# FPGA_POWER_AND_CONFIGURATION.net
KiCad netlist of a schematic drawn in Altium Designer
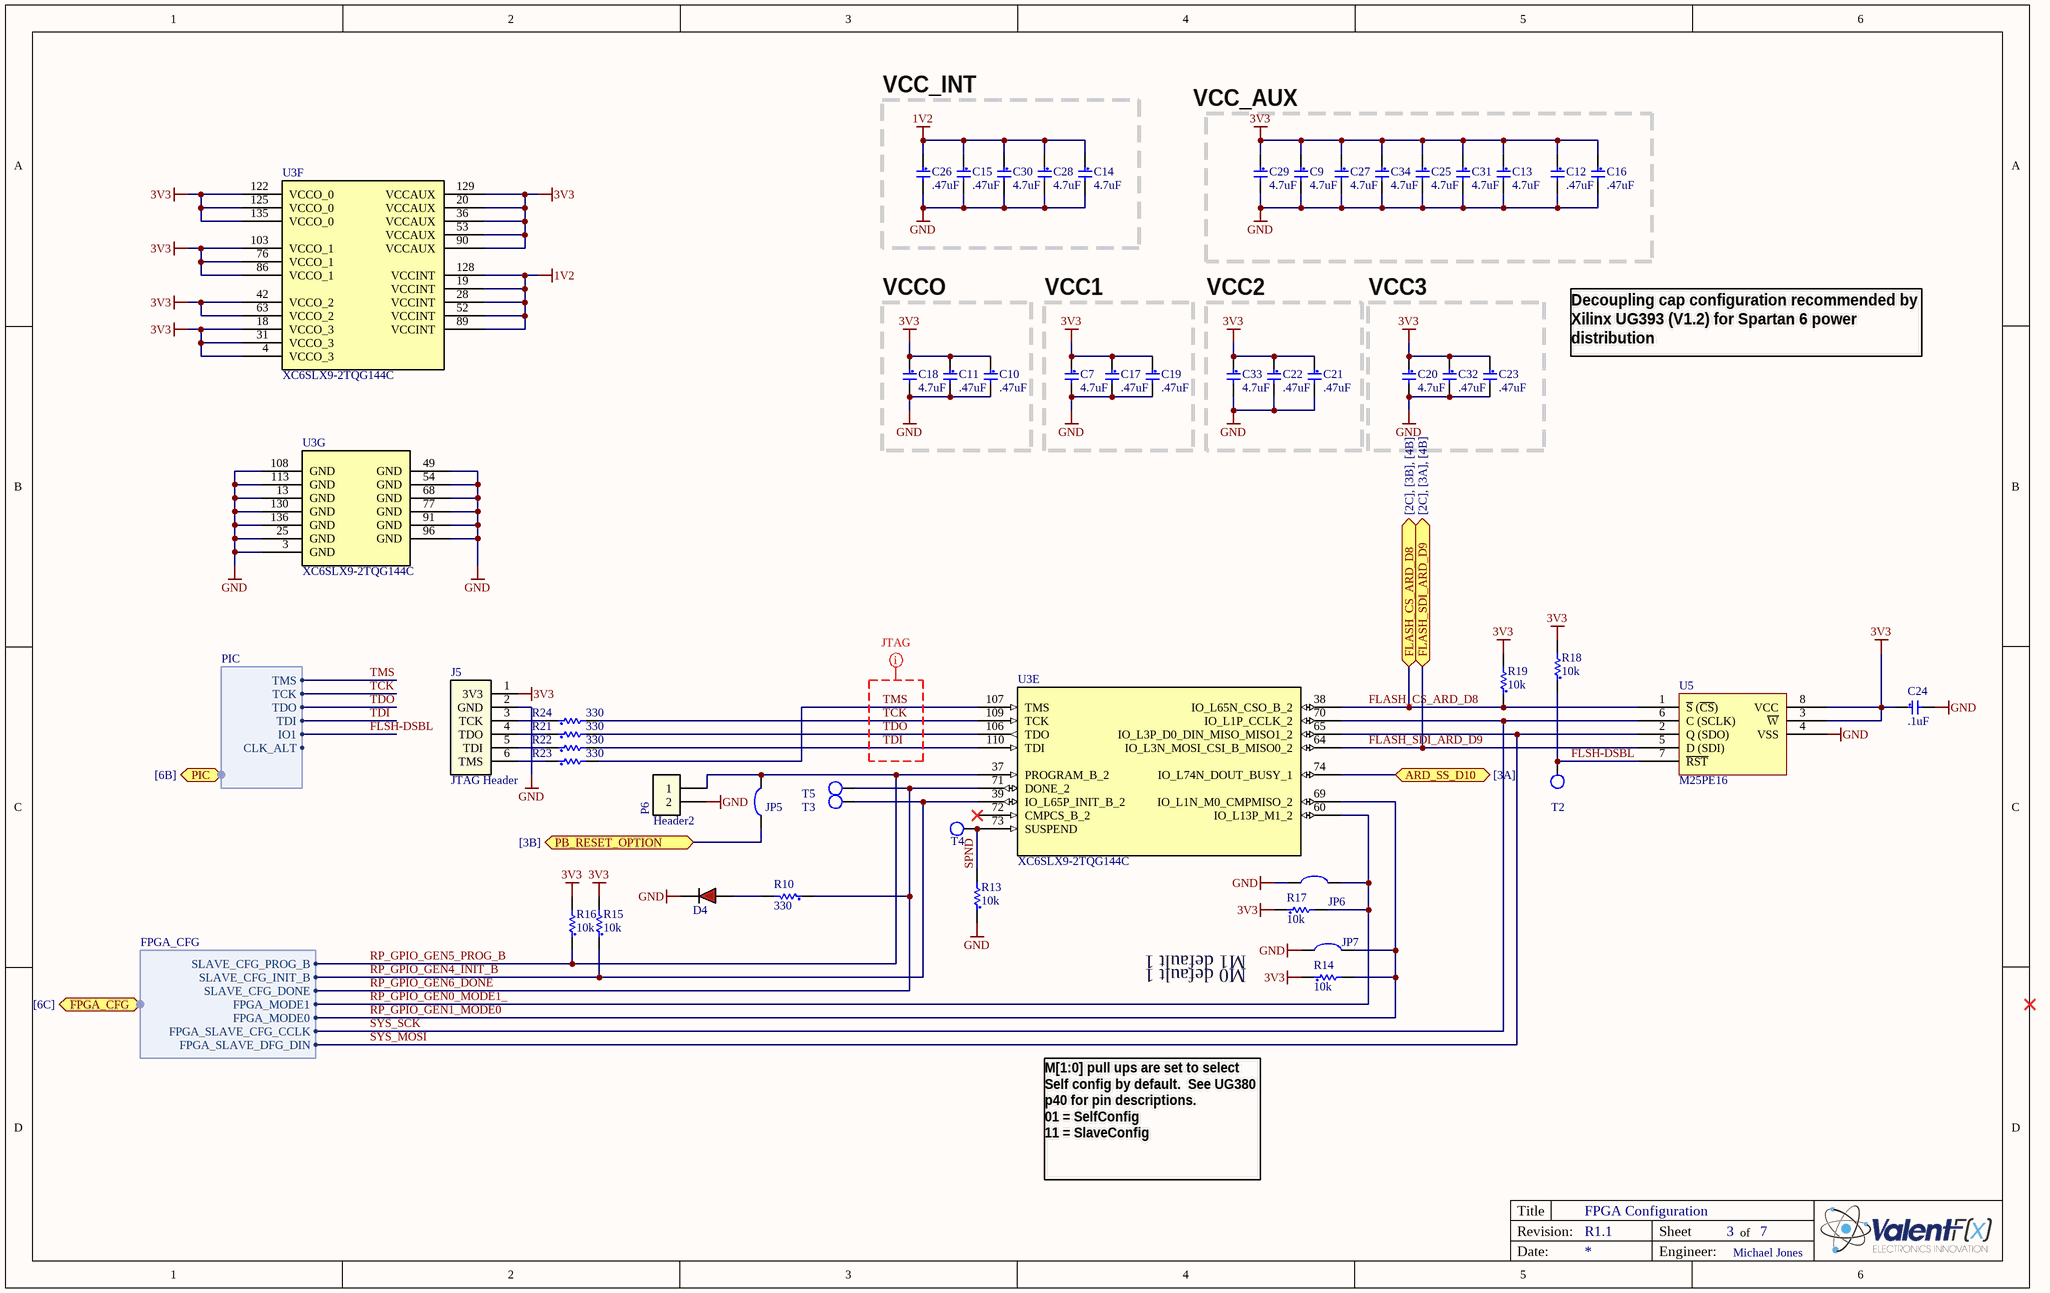
[diagram p0: FPGA_POWER_AND_CONFIGURATION.SchDoc]

(export (version "E")
  (design (tool "Eeschema 10.0.6"))
  (components
    (comp (ref "C7")
      (value "4.7uF")
      (footprint "C0603 - Marked")
      (description "4.7uF 6.3volts X5R 10% (MLCC) - SMD/SMT 0603")
      (fields
        (field (name "MANUFACTURER") "Murata Electronics North America")
        (field (name "MANUFACTURER PART NUMBER") "GRM188R60J475KE19D")
      )
      (libsource (lib "mCapacitors") (part "C0603 - GRM188R60J475KE19D"))
    )
    (comp (ref "C9")
      (value "4.7uF")
      (footprint "C0603 - Marked")
      (description "4.7uF 6.3volts X5R 10% (MLCC) - SMD/SMT 0603")
      (fields
        (field (name "MANUFACTURER") "Murata Electronics North America")
        (field (name "MANUFACTURER PART NUMBER") "GRM188R60J475KE19D")
      )
      (libsource (lib "mCapacitors") (part "C0603 - GRM188R60J475KE19D"))
    )
    (comp (ref "C10")
      (value ".47uF")
      (footprint "mRCL:C0603")
      (description ".47uF 25VDC X7R 10% SMD 0603 Paper T/R CERAMIC")
      (fields
        (field (name "MANUFACTURER") "Murata Electronics North America")
        (field (name "MANUFACTURER PART NUMBER") "GCM188R71E474KA64D")
      )
      (libsource (lib "mCapacitors") (part "C0603 - GCM188R71E474KA64D"))
    )
    (comp (ref "C11")
      (value ".47uF")
      (footprint "mRCL:C0603")
      (description ".47uF 25VDC X7R 10% SMD 0603 Paper T/R CERAMIC")
      (fields
        (field (name "MANUFACTURER") "Murata Electronics North America")
        (field (name "MANUFACTURER PART NUMBER") "GCM188R71E474KA64D")
      )
      (libsource (lib "mCapacitors") (part "C0603 - GCM188R71E474KA64D"))
    )
    (comp (ref "C12")
      (value ".47uF")
      (footprint "mRCL:C0603")
      (description ".47uF 25VDC X7R 10% SMD 0603 Paper T/R CERAMIC")
      (fields
        (field (name "MANUFACTURER") "Murata Electronics North America")
        (field (name "MANUFACTURER PART NUMBER") "GCM188R71E474KA64D")
      )
      (libsource (lib "mCapacitors") (part "C0603 - GCM188R71E474KA64D"))
    )
    (comp (ref "C13")
      (value "4.7uF")
      (footprint "C0603 - Marked")
      (description "4.7uF 6.3volts X5R 10% (MLCC) - SMD/SMT 0603")
      (fields
        (field (name "MANUFACTURER") "Murata Electronics North America")
        (field (name "MANUFACTURER PART NUMBER") "GRM188R60J475KE19D")
      )
      (libsource (lib "mCapacitors") (part "C0603 - GRM188R60J475KE19D"))
    )
    (comp (ref "C14")
      (value "4.7uF")
      (footprint "C0603 - Marked")
      (description "4.7uF 6.3volts X5R 10% (MLCC) - SMD/SMT 0603")
      (fields
        (field (name "MANUFACTURER") "Murata Electronics North America")
        (field (name "MANUFACTURER PART NUMBER") "GRM188R60J475KE19D")
      )
      (libsource (lib "mCapacitors") (part "C0603 - GRM188R60J475KE19D"))
    )
    (comp (ref "C15")
      (value ".47uF")
      (footprint "mRCL:C0603")
      (description ".47uF 25VDC X7R 10% SMD 0603 Paper T/R CERAMIC")
      (fields
        (field (name "MANUFACTURER") "Murata Electronics North America")
        (field (name "MANUFACTURER PART NUMBER") "GCM188R71E474KA64D")
      )
      (libsource (lib "mCapacitors") (part "C0603 - GCM188R71E474KA64D"))
    )
    (comp (ref "C16")
      (value ".47uF")
      (footprint "mRCL:C0603")
      (description ".47uF 25VDC X7R 10% SMD 0603 Paper T/R CERAMIC")
      (fields
        (field (name "MANUFACTURER") "Murata Electronics North America")
        (field (name "MANUFACTURER PART NUMBER") "GCM188R71E474KA64D")
      )
      (libsource (lib "mCapacitors") (part "C0603 - GCM188R71E474KA64D"))
    )
    (comp (ref "C17")
      (value ".47uF")
      (footprint "mRCL:C0603")
      (description ".47uF 25VDC X7R 10% SMD 0603 Paper T/R CERAMIC")
      (fields
        (field (name "MANUFACTURER") "Murata Electronics North America")
        (field (name "MANUFACTURER PART NUMBER") "GCM188R71E474KA64D")
      )
      (libsource (lib "mCapacitors") (part "C0603 - GCM188R71E474KA64D"))
    )
    (comp (ref "C18")
      (value "4.7uF")
      (footprint "C0603 - Marked")
      (description "4.7uF 6.3volts X5R 10% (MLCC) - SMD/SMT 0603")
      (fields
        (field (name "MANUFACTURER") "Murata Electronics North America")
        (field (name "MANUFACTURER PART NUMBER") "GRM188R60J475KE19D")
      )
      (libsource (lib "mCapacitors") (part "C0603 - GRM188R60J475KE19D"))
    )
    (comp (ref "C19")
      (value ".47uF")
      (footprint "mRCL:C0603")
      (description ".47uF 25VDC X7R 10% SMD 0603 Paper T/R CERAMIC")
      (fields
        (field (name "MANUFACTURER") "Murata Electronics North America")
        (field (name "MANUFACTURER PART NUMBER") "GCM188R71E474KA64D")
      )
      (libsource (lib "mCapacitors") (part "C0603 - GCM188R71E474KA64D"))
    )
    (comp (ref "C20")
      (value "4.7uF")
      (footprint "C0603 - Marked")
      (description "4.7uF 6.3volts X5R 10% (MLCC) - SMD/SMT 0603")
      (fields
        (field (name "MANUFACTURER") "Murata Electronics North America")
        (field (name "MANUFACTURER PART NUMBER") "GRM188R60J475KE19D")
      )
      (libsource (lib "mCapacitors") (part "C0603 - GRM188R60J475KE19D"))
    )
    (comp (ref "C21")
      (value ".47uF")
      (footprint "mRCL:C0603")
      (description ".47uF 25VDC X7R 10% SMD 0603 Paper T/R CERAMIC")
      (fields
        (field (name "MANUFACTURER") "Murata Electronics North America")
        (field (name "MANUFACTURER PART NUMBER") "GCM188R71E474KA64D")
      )
      (libsource (lib "mCapacitors") (part "C0603 - GCM188R71E474KA64D"))
    )
    (comp (ref "C22")
      (value ".47uF")
      (footprint "mRCL:C0603")
      (description ".47uF 25VDC X7R 10% SMD 0603 Paper T/R CERAMIC")
      (fields
        (field (name "MANUFACTURER") "Murata Electronics North America")
        (field (name "MANUFACTURER PART NUMBER") "GCM188R71E474KA64D")
      )
      (libsource (lib "mCapacitors") (part "C0603 - GCM188R71E474KA64D"))
    )
    (comp (ref "C23")
      (value ".47uF")
      (footprint "mRCL:C0603")
      (description ".47uF 25VDC X7R 10% SMD 0603 Paper T/R CERAMIC")
      (fields
        (field (name "MANUFACTURER") "Murata Electronics North America")
        (field (name "MANUFACTURER PART NUMBER") "GCM188R71E474KA64D")
      )
      (libsource (lib "mCapacitors") (part "C0603 - GCM188R71E474KA64D"))
    )
    (comp (ref "C24")
      (value ".1uF")
      (footprint "c0603")
      (description "CAP CER 0.1UF 25V Y5V 0603")
      (fields
        (field (name "MANUFACTURER") "Samsung Electro-Mechanics America, Inc")
        (field (name "MANUFACTURER PART NUMBER") "CL10F104ZA8NNNC")
      )
      (libsource (lib "mCapacitors") (part "C0603 - CL10F104ZA8NNNC"))
    )
    (comp (ref "C25")
      (value "4.7uF")
      (footprint "C0603 - Marked")
      (description "4.7uF 6.3volts X5R 10% (MLCC) - SMD/SMT 0603")
      (fields
        (field (name "MANUFACTURER") "Murata Electronics North America")
        (field (name "MANUFACTURER PART NUMBER") "GRM188R60J475KE19D")
      )
      (libsource (lib "mCapacitors") (part "C0603 - GRM188R60J475KE19D"))
    )
    (comp (ref "C26")
      (value ".47uF")
      (footprint "mRCL:C0603")
      (description ".47uF 25VDC X7R 10% SMD 0603 Paper T/R CERAMIC")
      (fields
        (field (name "MANUFACTURER") "Murata Electronics North America")
        (field (name "MANUFACTURER PART NUMBER") "GCM188R71E474KA64D")
      )
      (libsource (lib "mCapacitors") (part "C0603 - GCM188R71E474KA64D"))
    )
    (comp (ref "C27")
      (value "4.7uF")
      (footprint "C0603 - Marked")
      (description "4.7uF 6.3volts X5R 10% (MLCC) - SMD/SMT 0603")
      (fields
        (field (name "MANUFACTURER") "Murata Electronics North America")
        (field (name "MANUFACTURER PART NUMBER") "GRM188R60J475KE19D")
      )
      (libsource (lib "mCapacitors") (part "C0603 - GRM188R60J475KE19D"))
    )
    (comp (ref "C28")
      (value "4.7uF")
      (footprint "C0603 - Marked")
      (description "4.7uF 6.3volts X5R 10% (MLCC) - SMD/SMT 0603")
      (fields
        (field (name "MANUFACTURER") "Murata Electronics North America")
        (field (name "MANUFACTURER PART NUMBER") "GRM188R60J475KE19D")
      )
      (libsource (lib "mCapacitors") (part "C0603 - GRM188R60J475KE19D"))
    )
    (comp (ref "C29")
      (value "4.7uF")
      (footprint "C0603 - Marked")
      (description "4.7uF 6.3volts X5R 10% (MLCC) - SMD/SMT 0603")
      (fields
        (field (name "MANUFACTURER") "Murata Electronics North America")
        (field (name "MANUFACTURER PART NUMBER") "GRM188R60J475KE19D")
      )
      (libsource (lib "mCapacitors") (part "C0603 - GRM188R60J475KE19D"))
    )
    (comp (ref "C30")
      (value "4.7uF")
      (footprint "C0603 - Marked")
      (description "4.7uF 6.3volts X5R 10% (MLCC) - SMD/SMT 0603")
      (fields
        (field (name "MANUFACTURER") "Murata Electronics North America")
        (field (name "MANUFACTURER PART NUMBER") "GRM188R60J475KE19D")
      )
      (libsource (lib "mCapacitors") (part "C0603 - GRM188R60J475KE19D"))
    )
    (comp (ref "C31")
      (value "4.7uF")
      (footprint "C0603 - Marked")
      (description "4.7uF 6.3volts X5R 10% (MLCC) - SMD/SMT 0603")
      (fields
        (field (name "MANUFACTURER") "Murata Electronics North America")
        (field (name "MANUFACTURER PART NUMBER") "GRM188R60J475KE19D")
      )
      (libsource (lib "mCapacitors") (part "C0603 - GRM188R60J475KE19D"))
    )
    (comp (ref "C32")
      (value ".47uF")
      (footprint "mRCL:C0603")
      (description ".47uF 25VDC X7R 10% SMD 0603 Paper T/R CERAMIC")
      (fields
        (field (name "MANUFACTURER") "Murata Electronics North America")
        (field (name "MANUFACTURER PART NUMBER") "GCM188R71E474KA64D")
      )
      (libsource (lib "mCapacitors") (part "C0603 - GCM188R71E474KA64D"))
    )
    (comp (ref "C33")
      (value "4.7uF")
      (footprint "C0603 - Marked")
      (description "4.7uF 6.3volts X5R 10% (MLCC) - SMD/SMT 0603")
      (fields
        (field (name "MANUFACTURER") "Murata Electronics North America")
        (field (name "MANUFACTURER PART NUMBER") "GRM188R60J475KE19D")
      )
      (libsource (lib "mCapacitors") (part "C0603 - GRM188R60J475KE19D"))
    )
    (comp (ref "C34")
      (value "4.7uF")
      (footprint "C0603 - Marked")
      (description "4.7uF 6.3volts X5R 10% (MLCC) - SMD/SMT 0603")
      (fields
        (field (name "MANUFACTURER") "Murata Electronics North America")
        (field (name "MANUFACTURER PART NUMBER") "GRM188R60J475KE19D")
      )
      (libsource (lib "mCapacitors") (part "C0603 - GRM188R60J475KE19D"))
    )
    (comp (ref "D4")
      (value "598-8010-107F")
      (footprint "LED_0603 - RED")
      (description "LED ALINGAP RED CLEAR 0603 SMD")
      (fields (field (name "MANUFACTURER") "Dialight"))
      (libsource (lib "mDiode") (part "LED0603 - 598-8010-107F"))
    )
    (comp (ref "J5")
      (value "JTAG Header")
      (footprint "JTAG - Digilent HS1")
      (description "DIGILENT - 410-205 - PROGRAMMING CABLE, JTAG HS1, USB2")
      (fields
        (field (name "MANUFACTURER") "Samtec")
        (field (name "MANUFACTURER PART NUMBER") "TSW-106-08-G-S-RA")
      )
      (libsource (lib "mConnector") (part "JTAG - Digilent HS1"))
    )
    (comp (ref "JP5")
      (value "Solder Jumper")
      (footprint "SOLDER_JUMPER")
      (description "Solder/Configuration Jumper")
      (fields (field (name "MANUFACTURER") "n/a"))
      (libsource (lib "") (part "Solder Jumper_1"))
    )
    (comp (ref "JP6")
      (value "Solder Jumper")
      (footprint "SOLDER_JUMPER")
      (description "Solder/Configuration Jumper")
      (fields (field (name "MANUFACTURER") "n/a"))
      (libsource (lib "mConnector") (part "Solder Jumper"))
    )
    (comp (ref "JP7")
      (value "Solder Jumper")
      (footprint "SOLDER_JUMPER")
      (description "Solder/Configuration Jumper")
      (fields (field (name "MANUFACTURER") "n/a"))
      (libsource (lib "mConnector") (part "Solder Jumper"))
    )
    (comp (ref "P6")
      (value "Header2")
      (footprint "HEADER_2_40_100 THRU SIP")
      (description "Header 2 pin")
      (libsource (lib "mConnector") (part "Header2"))
    )
    (comp (ref "R10")
      (value "330")
      (footprint "R0603")
      (description "Thick Film Resistors - SMD 0603 330ohms 5% Tol")
      (fields
        (field (name "MANUFACTURER") "Panasonic")
        (field (name "MANUFACTURER PART NUMBER") "ERJ-3GEYJ331V")
      )
      (libsource (lib "") (part "R0603 - ERJ-3GEYJ331V_1"))
    )
    (comp (ref "R13")
      (value "10k")
      (footprint "mRCL:R0603")
      (description "10k Thick Film Resistors - SMD 1/10watt 10Kohms 1%")
      (fields
        (field (name "MANUFACTURER") "Vishay Dale")
        (field (name "MANUFACTURER PART NUMBER") "CRCW060310K0FKEA")
      )
      (libsource (lib "mResistors") (part "R0603 - CRCW060310K0FKEA"))
    )
    (comp (ref "R14")
      (value "10k")
      (footprint "mRCL:R0603")
      (description "10k Thick Film Resistors - SMD 1/10watt 10Kohms 1%")
      (fields
        (field (name "MANUFACTURER") "Vishay Dale")
        (field (name "MANUFACTURER PART NUMBER") "CRCW060310K0FKEA")
      )
      (libsource (lib "mResistors") (part "R0603 - CRCW060310K0FKEA"))
    )
    (comp (ref "R15")
      (value "10k")
      (footprint "mRCL:R0603")
      (description "10k Thick Film Resistors - SMD 1/10watt 10Kohms 1%")
      (fields
        (field (name "MANUFACTURER") "Vishay Dale")
        (field (name "MANUFACTURER PART NUMBER") "CRCW060310K0FKEA")
      )
      (libsource (lib "mResistors") (part "R0603 - CRCW060310K0FKEA"))
    )
    (comp (ref "R16")
      (value "10k")
      (footprint "mRCL:R0603")
      (description "10k Thick Film Resistors - SMD 1/10watt 10Kohms 1%")
      (fields
        (field (name "MANUFACTURER") "Vishay Dale")
        (field (name "MANUFACTURER PART NUMBER") "CRCW060310K0FKEA")
      )
      (libsource (lib "mResistors") (part "R0603 - CRCW060310K0FKEA"))
    )
    (comp (ref "R17")
      (value "10k")
      (footprint "mRCL:R0603")
      (description "10k Thick Film Resistors - SMD 1/10watt 10Kohms 1%")
      (fields
        (field (name "MANUFACTURER") "Vishay Dale")
        (field (name "MANUFACTURER PART NUMBER") "CRCW060310K0FKEA")
      )
      (libsource (lib "mResistors") (part "R0603 - CRCW060310K0FKEA"))
    )
    (comp (ref "R18")
      (value "10k")
      (footprint "mRCL:R0603")
      (description "10k Thick Film Resistors - SMD 1/10watt 10Kohms 1%")
      (fields
        (field (name "MANUFACTURER") "Vishay Dale")
        (field (name "MANUFACTURER PART NUMBER") "CRCW060310K0FKEA")
      )
      (libsource (lib "mResistors") (part "R0603 - CRCW060310K0FKEA"))
    )
    (comp (ref "R19")
      (value "10k")
      (footprint "mRCL:R0603")
      (description "10k Thick Film Resistors - SMD 1/10watt 10Kohms 1%")
      (fields
        (field (name "MANUFACTURER") "Vishay Dale")
        (field (name "MANUFACTURER PART NUMBER") "CRCW060310K0FKEA")
      )
      (libsource (lib "mResistors") (part "R0603 - CRCW060310K0FKEA"))
    )
    (comp (ref "R21")
      (value "330")
      (footprint "R0603")
      (description "Thick Film Resistors - SMD 0603 330ohms 5% Tol")
      (fields
        (field (name "MANUFACTURER") "Panasonic")
        (field (name "MANUFACTURER PART NUMBER") "ERJ-3GEYJ331V")
      )
      (libsource (lib "mResistors") (part "R0603 - ERJ-3GEYJ331V"))
    )
    (comp (ref "R22")
      (value "330")
      (footprint "R0603")
      (description "Thick Film Resistors - SMD 0603 330ohms 5% Tol")
      (fields
        (field (name "MANUFACTURER") "Panasonic")
        (field (name "MANUFACTURER PART NUMBER") "ERJ-3GEYJ331V")
      )
      (libsource (lib "mResistors") (part "R0603 - ERJ-3GEYJ331V"))
    )
    (comp (ref "R23")
      (value "330")
      (footprint "R0603")
      (description "Thick Film Resistors - SMD 0603 330ohms 5% Tol")
      (fields
        (field (name "MANUFACTURER") "Panasonic")
        (field (name "MANUFACTURER PART NUMBER") "ERJ-3GEYJ331V")
      )
      (libsource (lib "mResistors") (part "R0603 - ERJ-3GEYJ331V"))
    )
    (comp (ref "R24")
      (value "330")
      (footprint "R0603")
      (description "Thick Film Resistors - SMD 0603 330ohms 5% Tol")
      (fields
        (field (name "MANUFACTURER") "Panasonic")
        (field (name "MANUFACTURER PART NUMBER") "ERJ-3GEYJ331V")
      )
      (libsource (lib "mResistors") (part "R0603 - ERJ-3GEYJ331V"))
    )
    (comp (ref "T2")
      (value "Test Point")
      (footprint "Tp 25-40")
      (description "Test Point Smaller Symbol")
      (libsource (lib "mConnector") (part "Test Point 2"))
    )
    (comp (ref "T3")
      (value "Test Point")
      (footprint "Tp 25-40")
      (description "Test Point Smaller Symbol")
      (libsource (lib "mConnector") (part "Test Point 2"))
    )
    (comp (ref "T4")
      (value "Test Point")
      (footprint "Tp 25-40")
      (description "Test Point Smaller Symbol")
      (libsource (lib "mConnector") (part "Test Point 2"))
    )
    (comp (ref "T5")
      (value "Test Point")
      (footprint "Tp 25-40")
      (description "Test Point Smaller Symbol")
      (libsource (lib "mConnector") (part "Test Point 2"))
    )
    (comp (ref "U3")
      (value "XC6SLX9-2TQG144C")
      (footprint "TQ144_L")
      (description "IC FPAG SPARTAN 6 9K 144TQFP")
      (fields (field (name "MANUFACTURER") "Xilinx Inc"))
      (libsource (lib "mIC") (part "FPGA - XC6SLX9-2TQG144C"))
    )
    (comp (ref "U5")
      (value "M25PE16")
      (footprint "SOIC127P830X200-8L")
      (description "IC FLASH 16MBIT 75MHZ 8SOIC")
      (fields
        (field (name "MANUFACTURER") "Numonyx/ST Micro")
        (field (name "MANUFACTURER PART NUMBER") "M25PE16-VMW6TG")
      )
      (libsource (lib "ICs") (part "M25PE16-VMW6TG"))
    )
  )
  (nets
    (net (code "3") (name "/ARD_SS_D10") (class "Default")
      (node (ref "U3") (pin "74") (pinfunction "IO_L74N_DOUT_BUSY_1_74") (pintype "bidirectional"))
    )
    (net (code "4") (name "/FLASH_CS_ARD_D8") (class "Default")
      (node (ref "R19") (pin "1") (pinfunction "1_1") (pintype "passive"))
      (node (ref "U3") (pin "38") (pinfunction "IO_L65N_CSO_B_2_38") (pintype "bidirectional"))
      (node (ref "U5") (pin "1") (pinfunction "~{S}_(~{CS})_1") (pintype "passive"))
    )
    (net (code "5") (name "/FLASH_SDI_ARD_D9") (class "Default")
      (node (ref "U3") (pin "64") (pinfunction "IO_L3N_MOSI_CSI_B_MISO0_2_64") (pintype "bidirectional"))
      (node (ref "U5") (pin "5") (pinfunction "D_(SDI)_5") (pintype "passive"))
    )
    (net (code "6") (name "/FLSH-DSBL") (class "Default")
      (node (ref "R18") (pin "1") (pinfunction "1_1") (pintype "passive"))
      (node (ref "T2") (pin "1") (pinfunction "1_1") (pintype "passive"))
      (node (ref "U5") (pin "7") (pinfunction "~{RST}_7") (pintype "passive"))
    )
    (net (code "7") (name "/PB_RESET_OPTION") (class "Default")
      (node (ref "JP5") (pin "2") (pinfunction "2_2") (pintype "passive"))
    )
    (net (code "8") (name "/RP_GPIO_GEN0_MODE1_") (class "Default")
      (node (ref "JP6") (pin "1") (pinfunction "1_1") (pintype "passive"))
      (node (ref "R17") (pin "2") (pinfunction "2_2") (pintype "passive"))
      (node (ref "U3") (pin "60") (pinfunction "IO_L13P_M1_2_60") (pintype "bidirectional"))
    )
    (net (code "9") (name "/RP_GPIO_GEN1_MODE0") (class "Default")
      (node (ref "JP7") (pin "1") (pinfunction "1_1") (pintype "passive"))
      (node (ref "R14") (pin "2") (pinfunction "2_2") (pintype "passive"))
      (node (ref "U3") (pin "69") (pinfunction "IO_L1N_M0_CMPMISO_2_69") (pintype "bidirectional"))
    )
    (net (code "10") (name "/RP_GPIO_GEN4_INIT_B") (class "Default")
      (node (ref "R15") (pin "1") (pinfunction "1_1") (pintype "passive"))
      (node (ref "T3") (pin "1") (pinfunction "1_1") (pintype "passive"))
      (node (ref "U3") (pin "39") (pinfunction "IO_L65P_INIT_B_2_39") (pintype "bidirectional"))
    )
    (net (code "11") (name "/RP_GPIO_GEN5_PROG_B") (class "Default")
      (node (ref "JP5") (pin "1") (pinfunction "1_1") (pintype "passive"))
      (node (ref "P6") (pin "1") (pinfunction "1_1") (pintype "passive"))
      (node (ref "R16") (pin "1") (pinfunction "1_1") (pintype "passive"))
      (node (ref "U3") (pin "37") (pinfunction "PROGRAM_B_2_37") (pintype "input"))
    )
    (net (code "12") (name "/RP_GPIO_GEN6_DONE") (class "Default")
      (node (ref "R10") (pin "1") (pinfunction "1_1") (pintype "passive"))
      (node (ref "T5") (pin "1") (pinfunction "1_1") (pintype "passive"))
      (node (ref "U3") (pin "71") (pinfunction "DONE_2_71") (pintype "bidirectional"))
    )
    (net (code "13") (name "/SPND") (class "Default")
      (node (ref "R13") (pin "2") (pinfunction "2_2") (pintype "passive"))
      (node (ref "T4") (pin "1") (pinfunction "1_1") (pintype "passive"))
      (node (ref "U3") (pin "73") (pinfunction "SUSPEND_73") (pintype "input"))
    )
    (net (code "14") (name "/SYS_MOSI") (class "Default")
      (node (ref "U3") (pin "65") (pinfunction "IO_L3P_D0_DIN_MISO_MISO1_2_65") (pintype "bidirectional"))
      (node (ref "U5") (pin "2") (pinfunction "Q_(SDO)_2") (pintype "passive"))
    )
    (net (code "15") (name "/SYS_SCK") (class "Default")
      (node (ref "U3") (pin "70") (pinfunction "IO_L1P_CCLK_2_70") (pintype "bidirectional"))
      (node (ref "U5") (pin "6") (pinfunction "C_(SCLK)_6") (pintype "passive"))
    )
    (net (code "16") (name "/TCK") (class "Default")
      (node (ref "R24") (pin "2") (pinfunction "2_2") (pintype "passive"))
      (node (ref "U3") (pin "109") (pinfunction "TCK_109") (pintype "input"))
    )
    (net (code "17") (name "/TDI") (class "Default")
      (node (ref "R22") (pin "2") (pinfunction "2_2") (pintype "passive"))
      (node (ref "U3") (pin "110") (pinfunction "TDI_110") (pintype "input"))
    )
    (net (code "18") (name "/TDO") (class "Default")
      (node (ref "R21") (pin "2") (pinfunction "2_2") (pintype "passive"))
      (node (ref "U3") (pin "106") (pinfunction "TDO_106") (pintype "output"))
    )
    (net (code "19") (name "/TMS") (class "Default")
      (node (ref "R23") (pin "2") (pinfunction "2_2") (pintype "passive"))
      (node (ref "U3") (pin "107") (pinfunction "TMS_107") (pintype "input"))
    )
    (net (code "22") (name "1V2") (class "Default")
      (node (ref "C14") (pin "1") (pinfunction "1_1") (pintype "passive"))
      (node (ref "C15") (pin "1") (pinfunction "1_1") (pintype "passive"))
      (node (ref "C26") (pin "1") (pinfunction "1_1") (pintype "passive"))
      (node (ref "C28") (pin "1") (pinfunction "1_1") (pintype "passive"))
      (node (ref "C30") (pin "1") (pinfunction "1_1") (pintype "passive"))
      (node (ref "U3") (pin "128") (pinfunction "VCCINT_128") (pintype "power_in"))
      (node (ref "U3") (pin "19") (pinfunction "VCCINT_19") (pintype "power_in"))
      (node (ref "U3") (pin "28") (pinfunction "VCCINT_28") (pintype "power_in"))
      (node (ref "U3") (pin "52") (pinfunction "VCCINT_52") (pintype "power_in"))
      (node (ref "U3") (pin "89") (pinfunction "VCCINT_89") (pintype "power_in"))
    )
    (net (code "23") (name "3V3") (class "Default")
      (node (ref "C10") (pin "1") (pinfunction "1_1") (pintype "passive"))
      (node (ref "C11") (pin "1") (pinfunction "1_1") (pintype "passive"))
      (node (ref "C12") (pin "1") (pinfunction "1_1") (pintype "passive"))
      (node (ref "C13") (pin "1") (pinfunction "1_1") (pintype "passive"))
      (node (ref "C16") (pin "1") (pinfunction "1_1") (pintype "passive"))
      (node (ref "C17") (pin "1") (pinfunction "1_1") (pintype "passive"))
      (node (ref "C18") (pin "1") (pinfunction "1_1") (pintype "passive"))
      (node (ref "C19") (pin "1") (pinfunction "1_1") (pintype "passive"))
      (node (ref "C20") (pin "1") (pinfunction "1_1") (pintype "passive"))
      (node (ref "C21") (pin "1") (pinfunction "1_1") (pintype "passive"))
      (node (ref "C22") (pin "1") (pinfunction "1_1") (pintype "passive"))
      (node (ref "C23") (pin "1") (pinfunction "1_1") (pintype "passive"))
      (node (ref "C24") (pin "1") (pinfunction "1_1") (pintype "passive"))
      (node (ref "C25") (pin "1") (pinfunction "1_1") (pintype "passive"))
      (node (ref "C27") (pin "1") (pinfunction "1_1") (pintype "passive"))
      (node (ref "C29") (pin "1") (pinfunction "1_1") (pintype "passive"))
      (node (ref "C31") (pin "1") (pinfunction "1_1") (pintype "passive"))
      (node (ref "C32") (pin "1") (pinfunction "1_1") (pintype "passive"))
      (node (ref "C33") (pin "1") (pinfunction "1_1") (pintype "passive"))
      (node (ref "C34") (pin "1") (pinfunction "1_1") (pintype "passive"))
      (node (ref "C7") (pin "1") (pinfunction "1_1") (pintype "passive"))
      (node (ref "C9") (pin "1") (pinfunction "1_1") (pintype "passive"))
      (node (ref "J5") (pin "1") (pinfunction "3V3_1") (pintype "passive"))
      (node (ref "R14") (pin "1") (pinfunction "1_1") (pintype "passive"))
      (node (ref "R15") (pin "2") (pinfunction "2_2") (pintype "passive"))
      (node (ref "R16") (pin "2") (pinfunction "2_2") (pintype "passive"))
      (node (ref "R17") (pin "1") (pinfunction "1_1") (pintype "passive"))
      (node (ref "R18") (pin "2") (pinfunction "2_2") (pintype "passive"))
      (node (ref "R19") (pin "2") (pinfunction "2_2") (pintype "passive"))
      (node (ref "U3") (pin "103") (pinfunction "VCCO_1_103") (pintype "power_in"))
      (node (ref "U3") (pin "122") (pinfunction "VCCO_0_122") (pintype "power_in"))
      (node (ref "U3") (pin "125") (pinfunction "VCCO_0_125") (pintype "power_in"))
      (node (ref "U3") (pin "129") (pinfunction "VCCAUX_129") (pintype "power_in"))
      (node (ref "U3") (pin "135") (pinfunction "VCCO_0_135") (pintype "power_in"))
      (node (ref "U3") (pin "18") (pinfunction "VCCO_3_18") (pintype "power_in"))
      (node (ref "U3") (pin "20") (pinfunction "VCCAUX_20") (pintype "power_in"))
      (node (ref "U3") (pin "31") (pinfunction "VCCO_3_31") (pintype "power_in"))
      (node (ref "U3") (pin "36") (pinfunction "VCCAUX_36") (pintype "power_in"))
      (node (ref "U3") (pin "4") (pinfunction "VCCO_3_4") (pintype "power_in"))
      (node (ref "U3") (pin "42") (pinfunction "VCCO_2_42") (pintype "power_in"))
      (node (ref "U3") (pin "53") (pinfunction "VCCAUX_53") (pintype "power_in"))
      (node (ref "U3") (pin "63") (pinfunction "VCCO_2_63") (pintype "power_in"))
      (node (ref "U3") (pin "76") (pinfunction "VCCO_1_76") (pintype "power_in"))
      (node (ref "U3") (pin "86") (pinfunction "VCCO_1_86") (pintype "power_in"))
      (node (ref "U3") (pin "90") (pinfunction "VCCAUX_90") (pintype "power_in"))
      (node (ref "U5") (pin "3") (pinfunction "~{W}_3") (pintype "passive"))
      (node (ref "U5") (pin "8") (pinfunction "VCC_8") (pintype "passive"))
    )
    (net (code "24") (name "GND") (class "Default")
      (node (ref "C10") (pin "2") (pinfunction "2_2") (pintype "passive"))
      (node (ref "C11") (pin "2") (pinfunction "2_2") (pintype "passive"))
      (node (ref "C12") (pin "2") (pinfunction "2_2") (pintype "passive"))
      (node (ref "C13") (pin "2") (pinfunction "2_2") (pintype "passive"))
      (node (ref "C14") (pin "2") (pinfunction "2_2") (pintype "passive"))
      (node (ref "C15") (pin "2") (pinfunction "2_2") (pintype "passive"))
      (node (ref "C16") (pin "2") (pinfunction "2_2") (pintype "passive"))
      (node (ref "C17") (pin "2") (pinfunction "2_2") (pintype "passive"))
      (node (ref "C18") (pin "2") (pinfunction "2_2") (pintype "passive"))
      (node (ref "C19") (pin "2") (pinfunction "2_2") (pintype "passive"))
      (node (ref "C20") (pin "2") (pinfunction "2_2") (pintype "passive"))
      (node (ref "C21") (pin "2") (pinfunction "2_2") (pintype "passive"))
      (node (ref "C22") (pin "2") (pinfunction "2_2") (pintype "passive"))
      (node (ref "C23") (pin "2") (pinfunction "2_2") (pintype "passive"))
      (node (ref "C24") (pin "2") (pinfunction "2_2") (pintype "passive"))
      (node (ref "C25") (pin "2") (pinfunction "2_2") (pintype "passive"))
      (node (ref "C26") (pin "2") (pinfunction "2_2") (pintype "passive"))
      (node (ref "C27") (pin "2") (pinfunction "2_2") (pintype "passive"))
      (node (ref "C28") (pin "2") (pinfunction "2_2") (pintype "passive"))
      (node (ref "C29") (pin "2") (pinfunction "2_2") (pintype "passive"))
      (node (ref "C30") (pin "2") (pinfunction "2_2") (pintype "passive"))
      (node (ref "C31") (pin "2") (pinfunction "2_2") (pintype "passive"))
      (node (ref "C32") (pin "2") (pinfunction "2_2") (pintype "passive"))
      (node (ref "C33") (pin "2") (pinfunction "2_2") (pintype "passive"))
      (node (ref "C34") (pin "2") (pinfunction "2_2") (pintype "passive"))
      (node (ref "C7") (pin "2") (pinfunction "2_2") (pintype "passive"))
      (node (ref "C9") (pin "2") (pinfunction "2_2") (pintype "passive"))
      (node (ref "D4") (pin "C") (pinfunction "C_C") (pintype "passive"))
      (node (ref "J5") (pin "2") (pinfunction "GND_2") (pintype "passive"))
      (node (ref "JP6") (pin "2") (pinfunction "2_2") (pintype "passive"))
      (node (ref "JP7") (pin "2") (pinfunction "2_2") (pintype "passive"))
      (node (ref "P6") (pin "2") (pinfunction "2_2") (pintype "passive"))
      (node (ref "R13") (pin "1") (pinfunction "1_1") (pintype "passive"))
      (node (ref "U3") (pin "108") (pinfunction "GND_108") (pintype "power_in"))
      (node (ref "U3") (pin "113") (pinfunction "GND_113") (pintype "power_in"))
      (node (ref "U3") (pin "13") (pinfunction "GND_13") (pintype "power_in"))
      (node (ref "U3") (pin "130") (pinfunction "GND_130") (pintype "power_in"))
      (node (ref "U3") (pin "136") (pinfunction "GND_136") (pintype "power_in"))
      (node (ref "U3") (pin "25") (pinfunction "GND_25") (pintype "power_in"))
      (node (ref "U3") (pin "3") (pinfunction "GND_3") (pintype "power_in"))
      (node (ref "U3") (pin "49") (pinfunction "GND_49") (pintype "power_in"))
      (node (ref "U3") (pin "54") (pinfunction "GND_54") (pintype "power_in"))
      (node (ref "U3") (pin "68") (pinfunction "GND_68") (pintype "power_in"))
      (node (ref "U3") (pin "77") (pinfunction "GND_77") (pintype "power_in"))
      (node (ref "U3") (pin "91") (pinfunction "GND_91") (pintype "power_in"))
      (node (ref "U3") (pin "96") (pinfunction "GND_96") (pintype "power_in"))
      (node (ref "U5") (pin "4") (pinfunction "VSS_4") (pintype "passive"))
    )
    (net (code "25") (name "Net-(D4-PadA)") (class "Default")
      (node (ref "D4") (pin "A") (pinfunction "A_A") (pintype "passive"))
      (node (ref "R10") (pin "2") (pinfunction "2_2") (pintype "passive"))
    )
    (net (code "26") (name "Net-(J5-TCK)") (class "Default")
      (node (ref "J5") (pin "3") (pinfunction "TCK_3") (pintype "passive"))
      (node (ref "R24") (pin "1") (pinfunction "1_1") (pintype "passive"))
    )
    (net (code "27") (name "Net-(J5-TDI)") (class "Default")
      (node (ref "J5") (pin "5") (pinfunction "TDI_5") (pintype "passive"))
      (node (ref "R22") (pin "1") (pinfunction "1_1") (pintype "passive"))
    )
    (net (code "28") (name "Net-(J5-TDO)") (class "Default")
      (node (ref "J5") (pin "4") (pinfunction "TDO_4") (pintype "passive"))
      (node (ref "R21") (pin "1") (pinfunction "1_1") (pintype "passive"))
    )
    (net (code "29") (name "Net-(J5-TMS)") (class "Default")
      (node (ref "J5") (pin "6") (pinfunction "TMS_6") (pintype "passive"))
      (node (ref "R23") (pin "1") (pinfunction "1_1") (pintype "passive"))
    )
    (net (code "30") (name "unconnected-(U3E-CMPCS_B_2-Pad72)") (class "Default")
      (node (ref "U3") (pin "72") (pinfunction "CMPCS_B_2_72") (pintype "input+no_connect"))
    )
  )
)
